# dht_bme280.net
KiCad netlist of a schematic drawn in Altium Designer
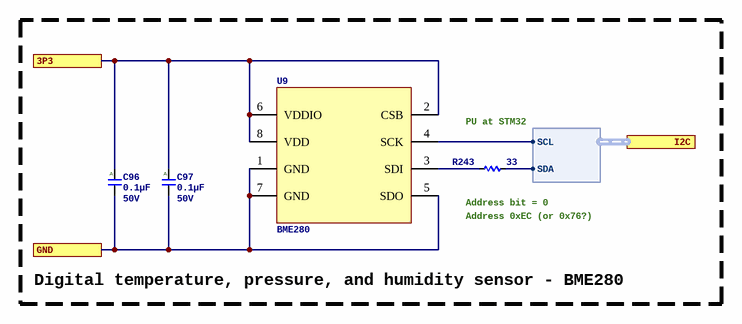
[diagram p0: dht_bme280.SchDoc]

(export (version "E")
  (design (tool "Eeschema 10.0.6"))
  (components
    (comp (ref "C96")
      (value "CGA2B3X7R1H104M050BB")
      (footprint "C0402_0.55MM")
      (description "CAP CER 0.1UF 50V X7R 0402")
      (fields
        (field (name "CAPACITANCE") "0.1µF")
        (field (name "VOLTAGE - RATED") "50V")
        (field (name "TOLERANCE") "±20%")
        (field (name "MANUFACTURER") "TDK Corporation")
      )
      (libsource (lib "sscp") (part "__template_cap_auto"))
    )
    (comp (ref "C97")
      (value "CGA2B3X7R1H104M050BB")
      (footprint "C0402_0.55MM")
      (description "CAP CER 0.1UF 50V X7R 0402")
      (fields
        (field (name "CAPACITANCE") "0.1µF")
        (field (name "VOLTAGE - RATED") "50V")
        (field (name "TOLERANCE") "±20%")
        (field (name "MANUFACTURER") "TDK Corporation")
      )
      (libsource (lib "sscp") (part "__template_cap_auto"))
    )
    (comp (ref "R243")
      (value "ERJ-2RKF33R0X")
      (footprint "R0402_0.40MM")
      (description "RES SMD 33 OHM 1% 1/10W 0402")
      (fields
        (field (name "RESISTANCE") "33")
        (field (name "TOLERANCE") "±1%")
        (field (name "MANUFACTURER") "Panasonic Electronic Components")
      )
      (libsource (lib "sscp") (part "__template_resistor"))
    )
    (comp (ref "U9")
      (value "BME280")
      (footprint "BOSCH_BME280")
      (description "Pressure, Temperature and Humidity Sensor Digital Output 1.8V 8-Pin LGA T/R")
      (fields (field (name "MANUFACTURER") "Bosch Tools"))
      (libsource (lib "SSCP") (part "DHT_SENSOR_BME280"))
    )
  )
  (nets
    (net (code "2") (name "/3P3") (class "Default")
      (node (ref "C96") (pin "1") (pintype "passive"))
      (node (ref "C97") (pin "1") (pintype "passive"))
      (node (ref "U9") (pin "2") (pinfunction "CSB_2") (pintype "passive"))
      (node (ref "U9") (pin "6") (pinfunction "VDDIO_6") (pintype "passive"))
      (node (ref "U9") (pin "8") (pinfunction "VDD_8") (pintype "passive"))
    )
    (net (code "3") (name "/GND") (class "Default")
      (node (ref "C96") (pin "2") (pintype "passive"))
      (node (ref "C97") (pin "2") (pintype "passive"))
      (node (ref "U9") (pin "1") (pinfunction "GND_1") (pintype "passive"))
      (node (ref "U9") (pin "5") (pinfunction "SDO_5") (pintype "passive"))
      (node (ref "U9") (pin "7") (pinfunction "GND_7") (pintype "passive"))
    )
    (net (code "4") (name "/SCL") (class "Default")
      (node (ref "U9") (pin "4") (pinfunction "SCK_4") (pintype "passive"))
    )
    (net (code "5") (name "/SDA") (class "Default") (node (ref "R243") (pin "1") (pintype "passive")))
    (net (code "7") (name "Net-(U9-SDI)") (class "Default")
      (node (ref "R243") (pin "2") (pintype "passive"))
      (node (ref "U9") (pin "3") (pinfunction "SDI_3") (pintype "passive"))
    )
  )
)
